# Driver.net
KiCad netlist of a schematic drawn in Altium Designer
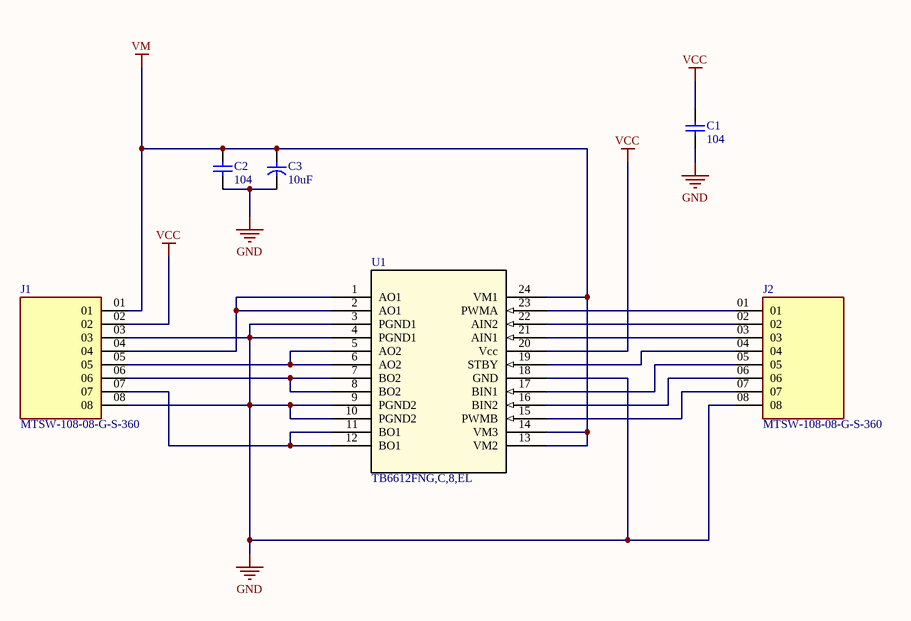
[diagram p0: Driver.SchDoc]

(export (version "E")
  (design (tool "Eeschema 10.0.6"))
  (components
    (comp (ref "C1")
      (value "104")
      (footprint "CAP Ceramic/W200")
      (description "Capacitor non-pol")
      (libsource (lib "chipfc_altium_libs") (part "Capacitor NP"))
    )
    (comp (ref "C2")
      (value "104")
      (footprint "CAP Ceramic/W200")
      (description "Capacitor non-pol")
      (libsource (lib "chipfc_altium_libs") (part "Capacitor NP"))
    )
    (comp (ref "C3")
      (value "10uF")
      (footprint "CAP/D80/H125/LS30")
      (description "Capacitor pol")
      (libsource (lib "chipfc_altium_libs") (part "Capacitor"))
    )
    (comp (ref "J1")
      (value "MTSW-108-08-G-S-360")
      (footprint "SAMTEC_MTSW-108-08-G-S-360")
      (libsource (lib "MTSW-108-08-G-S-360") (part "MTSW-108-08-G-S-360"))
    )
    (comp (ref "J2")
      (value "MTSW-108-08-G-S-360")
      (footprint "SAMTEC_MTSW-108-08-G-S-360")
      (libsource (lib "") (part "MTSW-108-08-G-S-360_1"))
    )
    (comp (ref "U1")
      (value "TB6612FNG,C,8,EL")
      (footprint "SSOP24-P-300-0p65A_TOS")
      (description "Description")
      (fields (field (name "COPYRIGHT") "Copyright (C) 2025 Ultra Librarian. All rights reserved."))
      (libsource (lib "NGHIA") (part "TB6612FNG,C,8,EL"))
    )
  )
  (nets
    (net (code "1") (name "GND") (class "Default")
      (node (ref "C1") (pin "2") (pinfunction "2_2") (pintype "passive"))
      (node (ref "C2") (pin "2") (pinfunction "2_2") (pintype "passive"))
      (node (ref "C3") (pin "2") (pinfunction "2_2") (pintype "passive"))
      (node (ref "J1") (pin "03") (pinfunction "03_03") (pintype "passive"))
      (node (ref "J1") (pin "08") (pinfunction "08_08") (pintype "passive"))
      (node (ref "J2") (pin "08") (pinfunction "08_08") (pintype "passive"))
      (node (ref "U1") (pin "10") (pinfunction "PGND2_10") (pintype "power_in"))
      (node (ref "U1") (pin "18") (pinfunction "GND_18") (pintype "power_in"))
      (node (ref "U1") (pin "3") (pinfunction "PGND1_3") (pintype "power_in"))
      (node (ref "U1") (pin "4") (pinfunction "PGND1_4") (pintype "power_in"))
      (node (ref "U1") (pin "9") (pinfunction "PGND2_9") (pintype "power_in"))
    )
    (net (code "2") (name "Net-(J1-Pad04)") (class "Default")
      (node (ref "J1") (pin "04") (pinfunction "04_04") (pintype "passive"))
      (node (ref "U1") (pin "1") (pinfunction "AO1_1") (pintype "passive"))
      (node (ref "U1") (pin "2") (pinfunction "AO1_2") (pintype "passive"))
    )
    (net (code "3") (name "Net-(J1-Pad05)") (class "Default")
      (node (ref "J1") (pin "05") (pinfunction "05_05") (pintype "passive"))
      (node (ref "U1") (pin "5") (pinfunction "AO2_5") (pintype "passive"))
      (node (ref "U1") (pin "6") (pinfunction "AO2_6") (pintype "passive"))
    )
    (net (code "4") (name "Net-(J1-Pad06)") (class "Default")
      (node (ref "J1") (pin "06") (pinfunction "06_06") (pintype "passive"))
      (node (ref "U1") (pin "7") (pinfunction "BO2_7") (pintype "passive"))
      (node (ref "U1") (pin "8") (pinfunction "BO2_8") (pintype "passive"))
    )
    (net (code "5") (name "Net-(J1-Pad07)") (class "Default")
      (node (ref "J1") (pin "07") (pinfunction "07_07") (pintype "passive"))
      (node (ref "U1") (pin "11") (pinfunction "BO1_11") (pintype "passive"))
      (node (ref "U1") (pin "12") (pinfunction "BO1_12") (pintype "passive"))
    )
    (net (code "6") (name "Net-(U1-AIN1)") (class "Default")
      (node (ref "J2") (pin "03") (pinfunction "03_03") (pintype "passive"))
      (node (ref "U1") (pin "21") (pinfunction "AIN1_21") (pintype "input"))
    )
    (net (code "7") (name "Net-(U1-AIN2)") (class "Default")
      (node (ref "J2") (pin "02") (pinfunction "02_02") (pintype "passive"))
      (node (ref "U1") (pin "22") (pinfunction "AIN2_22") (pintype "input"))
    )
    (net (code "8") (name "Net-(U1-BIN1)") (class "Default")
      (node (ref "J2") (pin "05") (pinfunction "05_05") (pintype "passive"))
      (node (ref "U1") (pin "17") (pinfunction "BIN1_17") (pintype "input"))
    )
    (net (code "9") (name "Net-(U1-BIN2)") (class "Default")
      (node (ref "J2") (pin "06") (pinfunction "06_06") (pintype "passive"))
      (node (ref "U1") (pin "16") (pinfunction "BIN2_16") (pintype "input"))
    )
    (net (code "10") (name "Net-(U1-PWMA)") (class "Default")
      (node (ref "J2") (pin "01") (pinfunction "01_01") (pintype "passive"))
      (node (ref "U1") (pin "23") (pinfunction "PWMA_23") (pintype "input"))
    )
    (net (code "11") (name "Net-(U1-PWMB)") (class "Default")
      (node (ref "J2") (pin "07") (pinfunction "07_07") (pintype "passive"))
      (node (ref "U1") (pin "15") (pinfunction "PWMB_15") (pintype "input"))
    )
    (net (code "12") (name "Net-(U1-STBY)") (class "Default")
      (node (ref "J2") (pin "04") (pinfunction "04_04") (pintype "passive"))
      (node (ref "U1") (pin "19") (pinfunction "STBY_19") (pintype "input"))
    )
    (net (code "13") (name "VCC") (class "Default")
      (node (ref "C1") (pin "1") (pinfunction "1_1") (pintype "passive"))
      (node (ref "J1") (pin "02") (pinfunction "02_02") (pintype "passive"))
      (node (ref "U1") (pin "20") (pinfunction "Vcc_20") (pintype "power_in"))
    )
    (net (code "14") (name "VM") (class "Default")
      (node (ref "C2") (pin "1") (pinfunction "1_1") (pintype "passive"))
      (node (ref "C3") (pin "1") (pinfunction "1_1") (pintype "passive"))
      (node (ref "J1") (pin "01") (pinfunction "01_01") (pintype "passive"))
      (node (ref "U1") (pin "13") (pinfunction "VM2_13") (pintype "power_in"))
      (node (ref "U1") (pin "14") (pinfunction "VM3_14") (pintype "power_in"))
      (node (ref "U1") (pin "24") (pinfunction "VM1_24") (pintype "power_in"))
    )
  )
)
